# carousel.net
KiCad netlist of a schematic drawn in EAGLE
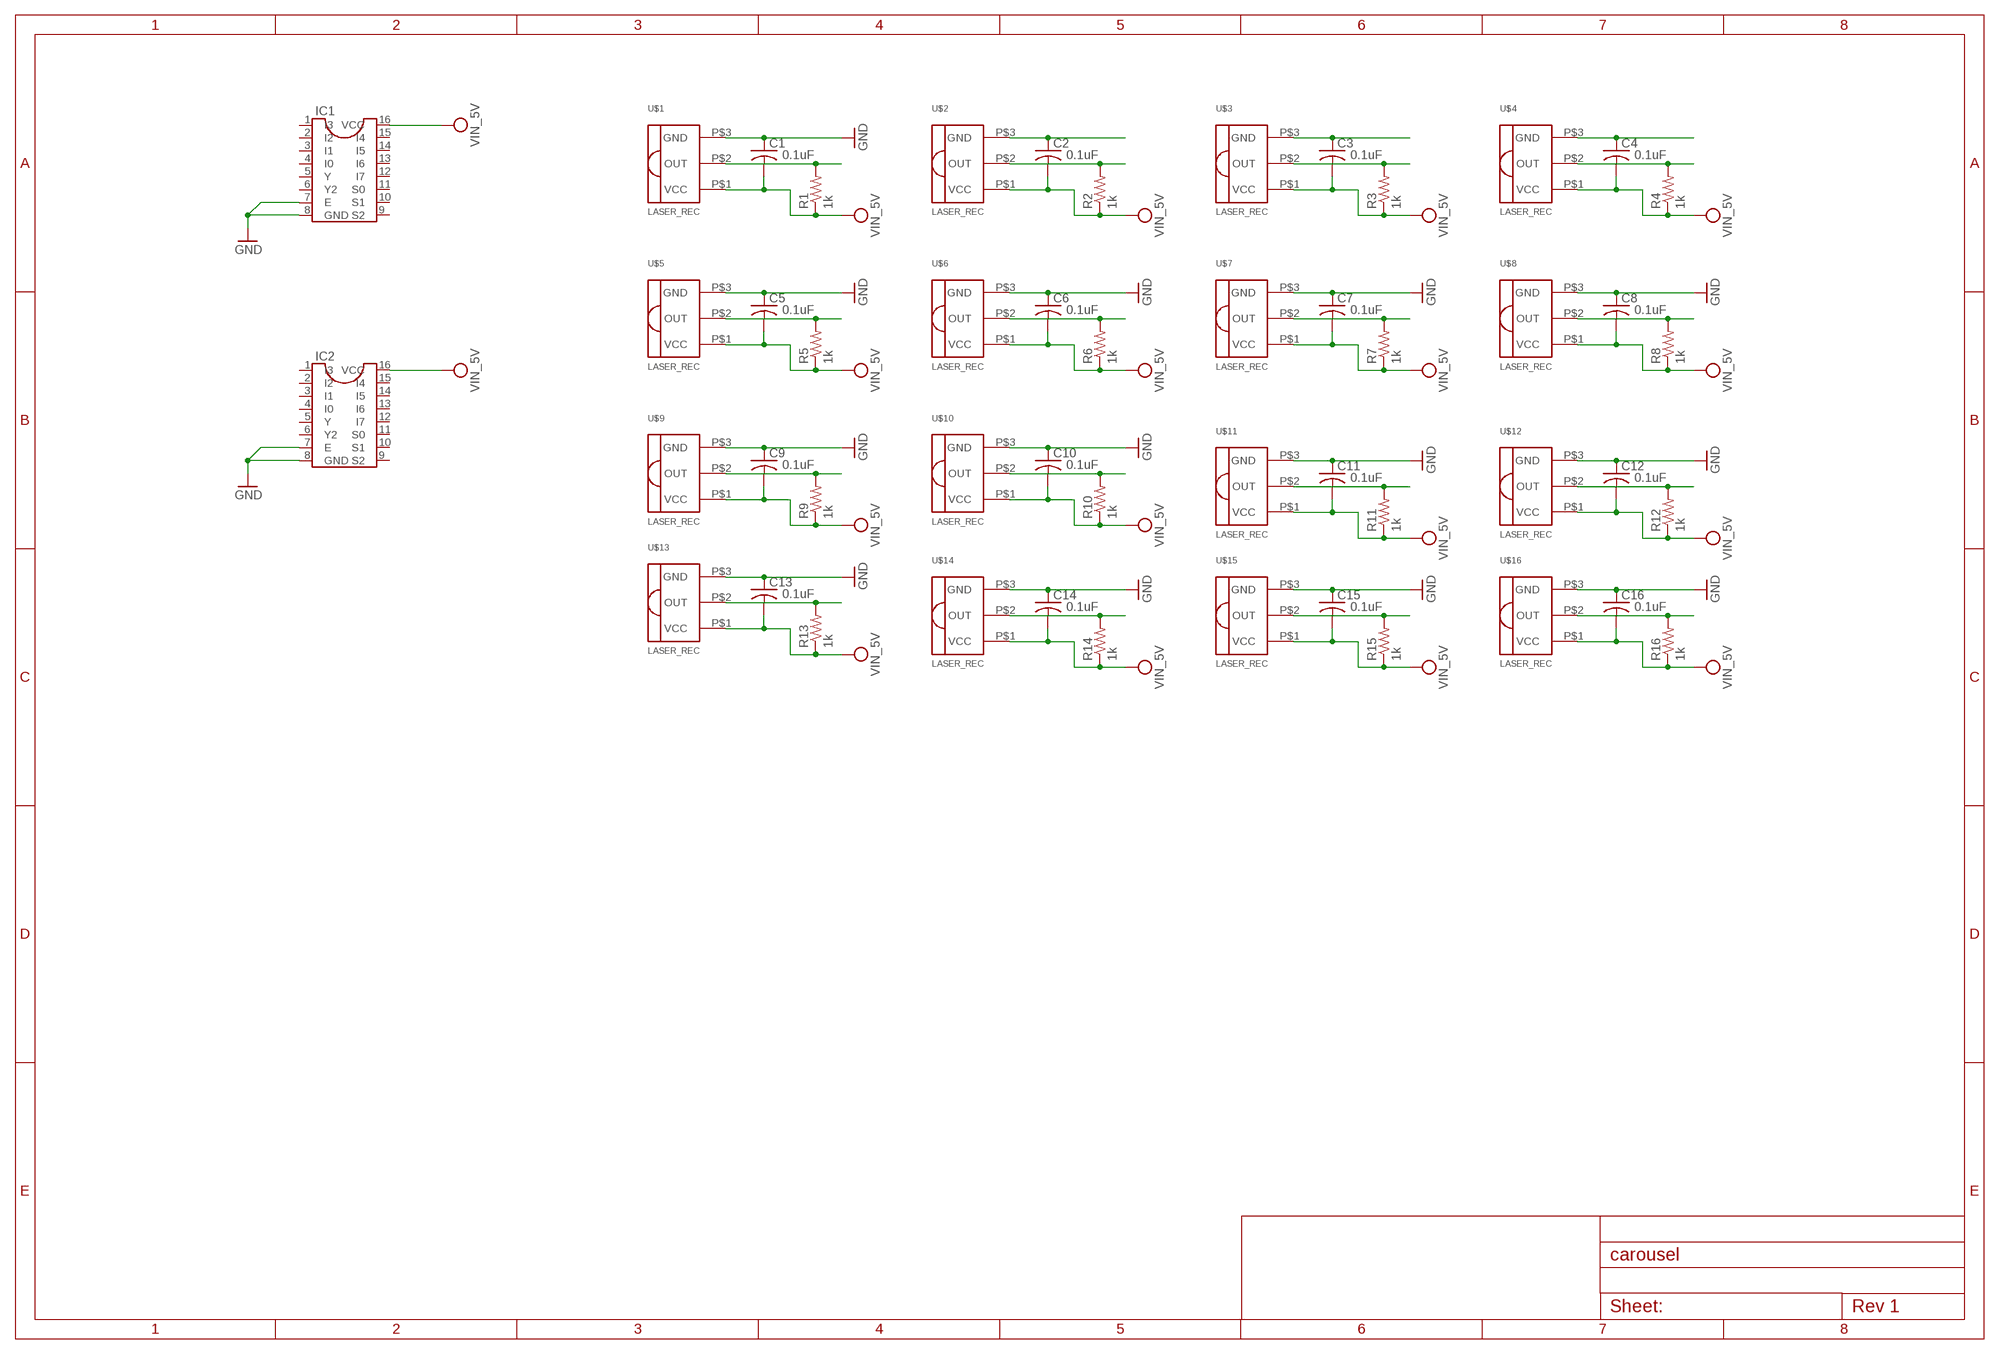
[diagram p0: schematic, sheet 1]

(export (version "E")
  (design (tool "Eeschema 10.0.6"))
  (components
    (comp (ref "C1")
      (value "0.1uF")
      (footprint "eagle-import:C025-024X044")
      (libsource (lib "eagle-import") (part "C-US025-024X044"))
    )
    (comp (ref "C2")
      (value "0.1uF")
      (footprint "eagle-import:C025-024X044")
      (libsource (lib "eagle-import") (part "C-US025-024X044"))
    )
    (comp (ref "C3")
      (value "0.1uF")
      (footprint "eagle-import:C025-024X044")
      (libsource (lib "eagle-import") (part "C-US025-024X044"))
    )
    (comp (ref "C4")
      (value "0.1uF")
      (footprint "eagle-import:C025-024X044")
      (libsource (lib "eagle-import") (part "C-US025-024X044"))
    )
    (comp (ref "C5")
      (value "0.1uF")
      (footprint "eagle-import:C025-024X044")
      (libsource (lib "eagle-import") (part "C-US025-024X044"))
    )
    (comp (ref "C6")
      (value "0.1uF")
      (footprint "eagle-import:C025-024X044")
      (libsource (lib "eagle-import") (part "C-US025-024X044"))
    )
    (comp (ref "C7")
      (value "0.1uF")
      (footprint "eagle-import:C025-024X044")
      (libsource (lib "eagle-import") (part "C-US025-024X044"))
    )
    (comp (ref "C8")
      (value "0.1uF")
      (footprint "eagle-import:C025-024X044")
      (libsource (lib "eagle-import") (part "C-US025-024X044"))
    )
    (comp (ref "C9")
      (value "0.1uF")
      (footprint "eagle-import:C025-024X044")
      (libsource (lib "eagle-import") (part "C-US025-024X044"))
    )
    (comp (ref "C10")
      (value "0.1uF")
      (footprint "eagle-import:C025-024X044")
      (libsource (lib "eagle-import") (part "C-US025-024X044"))
    )
    (comp (ref "C11")
      (value "0.1uF")
      (footprint "eagle-import:C025-024X044")
      (libsource (lib "eagle-import") (part "C-US025-024X044"))
    )
    (comp (ref "C12")
      (value "0.1uF")
      (footprint "eagle-import:C050-024X044")
      (libsource (lib "eagle-import") (part "C-US050-024X044"))
    )
    (comp (ref "C13")
      (value "0.1uF")
      (footprint "eagle-import:C025-024X044")
      (libsource (lib "eagle-import") (part "C-US025-024X044"))
    )
    (comp (ref "C14")
      (value "0.1uF")
      (footprint "eagle-import:C025-024X044")
      (libsource (lib "eagle-import") (part "C-US025-024X044"))
    )
    (comp (ref "C15")
      (value "0.1uF")
      (footprint "eagle-import:C025-024X044")
      (libsource (lib "eagle-import") (part "C-US025-024X044"))
    )
    (comp (ref "C16")
      (value "0.1uF")
      (footprint "eagle-import:C025-024X044")
      (libsource (lib "eagle-import") (part "C-US025-024X044"))
    )
    (comp (ref "IC1")
      (value "CD74HCT151S")
      (footprint "eagle-import:CD74HCT151")
      (libsource (lib "eagle-import") (part "CD74HCT151S"))
    )
    (comp (ref "IC2")
      (value "CD74HCT151S")
      (footprint "eagle-import:CD74HCT151")
      (libsource (lib "eagle-import") (part "CD74HCT151S"))
    )
    (comp (ref "R1")
      (value "1k")
      (footprint "eagle-import:0204V")
      (libsource (lib "eagle-import") (part "R-US_0204/2V"))
    )
    (comp (ref "R2")
      (value "1k")
      (footprint "eagle-import:0204V")
      (libsource (lib "eagle-import") (part "R-US_0204/2V"))
    )
    (comp (ref "R3")
      (value "1k")
      (footprint "eagle-import:0204V")
      (libsource (lib "eagle-import") (part "R-US_0204/2V"))
    )
    (comp (ref "R4")
      (value "1k")
      (footprint "eagle-import:0204V")
      (libsource (lib "eagle-import") (part "R-US_0204/2V"))
    )
    (comp (ref "R5")
      (value "1k")
      (footprint "eagle-import:0204V")
      (libsource (lib "eagle-import") (part "R-US_0204/2V"))
    )
    (comp (ref "R6")
      (value "1k")
      (footprint "eagle-import:0204V")
      (libsource (lib "eagle-import") (part "R-US_0204/2V"))
    )
    (comp (ref "R7")
      (value "1k")
      (footprint "eagle-import:0204V")
      (libsource (lib "eagle-import") (part "R-US_0204/2V"))
    )
    (comp (ref "R8")
      (value "1k")
      (footprint "eagle-import:0204V")
      (libsource (lib "eagle-import") (part "R-US_0204/2V"))
    )
    (comp (ref "R9")
      (value "1k")
      (footprint "eagle-import:0204V")
      (libsource (lib "eagle-import") (part "R-US_0204/2V"))
    )
    (comp (ref "R10")
      (value "1k")
      (footprint "eagle-import:0204V")
      (libsource (lib "eagle-import") (part "R-US_0204/2V"))
    )
    (comp (ref "R11")
      (value "1k")
      (footprint "eagle-import:0204V")
      (libsource (lib "eagle-import") (part "R-US_0204/2V"))
    )
    (comp (ref "R12")
      (value "1k")
      (footprint "eagle-import:0204V")
      (libsource (lib "eagle-import") (part "R-US_0204/2V"))
    )
    (comp (ref "R13")
      (value "1k")
      (footprint "eagle-import:0204V")
      (libsource (lib "eagle-import") (part "R-US_0204/2V"))
    )
    (comp (ref "R14")
      (value "1k")
      (footprint "eagle-import:0204V")
      (libsource (lib "eagle-import") (part "R-US_0204/2V"))
    )
    (comp (ref "R15")
      (value "1k")
      (footprint "eagle-import:0204V")
      (libsource (lib "eagle-import") (part "R-US_0204/2V"))
    )
    (comp (ref "R16")
      (value "1k")
      (footprint "eagle-import:0204V")
      (libsource (lib "eagle-import") (part "R-US_0204/2V"))
    )
    (comp (ref "U$1")
      (value "LASER_REC")
      (footprint "eagle-import:LSR_RC")
      (libsource (lib "eagle-import") (part "LASER_REC"))
    )
    (comp (ref "U$2")
      (value "LASER_REC")
      (footprint "eagle-import:LSR_RC")
      (libsource (lib "eagle-import") (part "LASER_REC"))
    )
    (comp (ref "U$3")
      (value "LASER_REC")
      (footprint "eagle-import:LSR_RC")
      (libsource (lib "eagle-import") (part "LASER_REC"))
    )
    (comp (ref "U$4")
      (value "LASER_REC")
      (footprint "eagle-import:LSR_RC")
      (libsource (lib "eagle-import") (part "LASER_REC"))
    )
    (comp (ref "U$5")
      (value "LASER_REC")
      (footprint "eagle-import:LSR_RC")
      (libsource (lib "eagle-import") (part "LASER_REC"))
    )
    (comp (ref "U$6")
      (value "LASER_REC")
      (footprint "eagle-import:LSR_RC")
      (libsource (lib "eagle-import") (part "LASER_REC"))
    )
    (comp (ref "U$7")
      (value "LASER_REC")
      (footprint "eagle-import:LSR_RC")
      (libsource (lib "eagle-import") (part "LASER_REC"))
    )
    (comp (ref "U$8")
      (value "LASER_REC")
      (footprint "eagle-import:LSR_RC")
      (libsource (lib "eagle-import") (part "LASER_REC"))
    )
    (comp (ref "U$9")
      (value "LASER_REC")
      (footprint "eagle-import:LSR_RC")
      (libsource (lib "eagle-import") (part "LASER_REC"))
    )
    (comp (ref "U$10")
      (value "LASER_REC")
      (footprint "eagle-import:LSR_RC")
      (libsource (lib "eagle-import") (part "LASER_REC"))
    )
    (comp (ref "U$11")
      (value "LASER_REC")
      (footprint "eagle-import:LSR_RC")
      (libsource (lib "eagle-import") (part "LASER_REC"))
    )
    (comp (ref "U$12")
      (value "LASER_REC")
      (footprint "eagle-import:LSR_RC")
      (libsource (lib "eagle-import") (part "LASER_REC"))
    )
    (comp (ref "U$13")
      (value "LASER_REC")
      (footprint "eagle-import:LSR_RC")
      (libsource (lib "eagle-import") (part "LASER_REC"))
    )
    (comp (ref "U$14")
      (value "LASER_REC")
      (footprint "eagle-import:LSR_RC")
      (libsource (lib "eagle-import") (part "LASER_REC"))
    )
    (comp (ref "U$15")
      (value "LASER_REC")
      (footprint "eagle-import:LSR_RC")
      (libsource (lib "eagle-import") (part "LASER_REC"))
    )
    (comp (ref "U$16")
      (value "LASER_REC")
      (footprint "eagle-import:LSR_RC")
      (libsource (lib "eagle-import") (part "LASER_REC"))
    )
  )
  (nets
    (net (code "1") (name "GND") (class "Default")
      (node (ref "C1") (pin "1") (pinfunction "1_1") (pintype "passive"))
      (node (ref "C10") (pin "1") (pinfunction "1_1") (pintype "passive"))
      (node (ref "C11") (pin "1") (pinfunction "1_1") (pintype "passive"))
      (node (ref "C12") (pin "1") (pinfunction "1_1") (pintype "passive"))
      (node (ref "C13") (pin "1") (pinfunction "1_1") (pintype "passive"))
      (node (ref "C14") (pin "1") (pinfunction "1_1") (pintype "passive"))
      (node (ref "C15") (pin "1") (pinfunction "1_1") (pintype "passive"))
      (node (ref "C16") (pin "1") (pinfunction "1_1") (pintype "passive"))
      (node (ref "C5") (pin "1") (pinfunction "1_1") (pintype "passive"))
      (node (ref "C6") (pin "1") (pinfunction "1_1") (pintype "passive"))
      (node (ref "C7") (pin "1") (pinfunction "1_1") (pintype "passive"))
      (node (ref "C8") (pin "1") (pinfunction "1_1") (pintype "passive"))
      (node (ref "C9") (pin "1") (pinfunction "1_1") (pintype "passive"))
      (node (ref "IC1") (pin "7") (pinfunction "E_7") (pintype "power_in"))
      (node (ref "IC1") (pin "8") (pinfunction "GND_8") (pintype "power_in"))
      (node (ref "IC2") (pin "7") (pinfunction "E_7") (pintype "power_in"))
      (node (ref "IC2") (pin "8") (pinfunction "GND_8") (pintype "power_in"))
      (node (ref "U$1") (pin "P$3") (pinfunction "GND_P$3") (pintype "power_in"))
      (node (ref "U$10") (pin "P$3") (pinfunction "GND_P$3") (pintype "power_in"))
      (node (ref "U$11") (pin "P$3") (pinfunction "GND_P$3") (pintype "power_in"))
      (node (ref "U$12") (pin "P$3") (pinfunction "GND_P$3") (pintype "power_in"))
      (node (ref "U$13") (pin "P$3") (pinfunction "GND_P$3") (pintype "power_in"))
      (node (ref "U$14") (pin "P$3") (pinfunction "GND_P$3") (pintype "power_in"))
      (node (ref "U$15") (pin "P$3") (pinfunction "GND_P$3") (pintype "power_in"))
      (node (ref "U$16") (pin "P$3") (pinfunction "GND_P$3") (pintype "power_in"))
      (node (ref "U$5") (pin "P$3") (pinfunction "GND_P$3") (pintype "power_in"))
      (node (ref "U$6") (pin "P$3") (pinfunction "GND_P$3") (pintype "power_in"))
      (node (ref "U$7") (pin "P$3") (pinfunction "GND_P$3") (pintype "power_in"))
      (node (ref "U$8") (pin "P$3") (pinfunction "GND_P$3") (pintype "power_in"))
      (node (ref "U$9") (pin "P$3") (pinfunction "GND_P$3") (pintype "power_in"))
    )
    (net (code "2") (name "Net-(U$1-OUT)") (class "Default")
      (node (ref "R1") (pin "2") (pinfunction "2_2") (pintype "passive"))
      (node (ref "U$1") (pin "P$2") (pinfunction "OUT_P$2") (pintype "output"))
    )
    (net (code "3") (name "Net-(U$2-GND)") (class "Default")
      (node (ref "C2") (pin "1") (pinfunction "1_1") (pintype "passive"))
      (node (ref "U$2") (pin "P$3") (pinfunction "GND_P$3") (pintype "power_in"))
    )
    (net (code "4") (name "Net-(U$2-OUT)") (class "Default")
      (node (ref "R2") (pin "2") (pinfunction "2_2") (pintype "passive"))
      (node (ref "U$2") (pin "P$2") (pinfunction "OUT_P$2") (pintype "output"))
    )
    (net (code "5") (name "Net-(U$3-GND)") (class "Default")
      (node (ref "C3") (pin "1") (pinfunction "1_1") (pintype "passive"))
      (node (ref "U$3") (pin "P$3") (pinfunction "GND_P$3") (pintype "power_in"))
    )
    (net (code "6") (name "Net-(U$3-OUT)") (class "Default")
      (node (ref "R3") (pin "2") (pinfunction "2_2") (pintype "passive"))
      (node (ref "U$3") (pin "P$2") (pinfunction "OUT_P$2") (pintype "output"))
    )
    (net (code "7") (name "Net-(U$4-GND)") (class "Default")
      (node (ref "C4") (pin "1") (pinfunction "1_1") (pintype "passive"))
      (node (ref "U$4") (pin "P$3") (pinfunction "GND_P$3") (pintype "power_in"))
    )
    (net (code "8") (name "Net-(U$4-OUT)") (class "Default")
      (node (ref "R4") (pin "2") (pinfunction "2_2") (pintype "passive"))
      (node (ref "U$4") (pin "P$2") (pinfunction "OUT_P$2") (pintype "output"))
    )
    (net (code "9") (name "Net-(U$5-OUT)") (class "Default")
      (node (ref "R5") (pin "2") (pinfunction "2_2") (pintype "passive"))
      (node (ref "U$5") (pin "P$2") (pinfunction "OUT_P$2") (pintype "output"))
    )
    (net (code "10") (name "Net-(U$6-OUT)") (class "Default")
      (node (ref "R6") (pin "2") (pinfunction "2_2") (pintype "passive"))
      (node (ref "U$6") (pin "P$2") (pinfunction "OUT_P$2") (pintype "output"))
    )
    (net (code "11") (name "Net-(U$7-OUT)") (class "Default")
      (node (ref "R7") (pin "2") (pinfunction "2_2") (pintype "passive"))
      (node (ref "U$7") (pin "P$2") (pinfunction "OUT_P$2") (pintype "output"))
    )
    (net (code "12") (name "Net-(U$8-OUT)") (class "Default")
      (node (ref "R8") (pin "2") (pinfunction "2_2") (pintype "passive"))
      (node (ref "U$8") (pin "P$2") (pinfunction "OUT_P$2") (pintype "output"))
    )
    (net (code "13") (name "Net-(U$9-OUT)") (class "Default")
      (node (ref "R9") (pin "2") (pinfunction "2_2") (pintype "passive"))
      (node (ref "U$9") (pin "P$2") (pinfunction "OUT_P$2") (pintype "output"))
    )
    (net (code "14") (name "Net-(U$10-OUT)") (class "Default")
      (node (ref "R10") (pin "2") (pinfunction "2_2") (pintype "passive"))
      (node (ref "U$10") (pin "P$2") (pinfunction "OUT_P$2") (pintype "output"))
    )
    (net (code "15") (name "Net-(U$11-OUT)") (class "Default")
      (node (ref "R11") (pin "2") (pinfunction "2_2") (pintype "passive"))
      (node (ref "U$11") (pin "P$2") (pinfunction "OUT_P$2") (pintype "output"))
    )
    (net (code "16") (name "Net-(U$12-OUT)") (class "Default")
      (node (ref "R12") (pin "2") (pinfunction "2_2") (pintype "passive"))
      (node (ref "U$12") (pin "P$2") (pinfunction "OUT_P$2") (pintype "output"))
    )
    (net (code "17") (name "Net-(U$13-OUT)") (class "Default")
      (node (ref "R13") (pin "2") (pinfunction "2_2") (pintype "passive"))
      (node (ref "U$13") (pin "P$2") (pinfunction "OUT_P$2") (pintype "output"))
    )
    (net (code "18") (name "Net-(U$14-OUT)") (class "Default")
      (node (ref "R14") (pin "2") (pinfunction "2_2") (pintype "passive"))
      (node (ref "U$14") (pin "P$2") (pinfunction "OUT_P$2") (pintype "output"))
    )
    (net (code "19") (name "Net-(U$15-OUT)") (class "Default")
      (node (ref "R15") (pin "2") (pinfunction "2_2") (pintype "passive"))
      (node (ref "U$15") (pin "P$2") (pinfunction "OUT_P$2") (pintype "output"))
    )
    (net (code "20") (name "Net-(U$16-OUT)") (class "Default")
      (node (ref "R16") (pin "2") (pinfunction "2_2") (pintype "passive"))
      (node (ref "U$16") (pin "P$2") (pinfunction "OUT_P$2") (pintype "output"))
    )
    (net (code "21") (name "VIN_5V") (class "Default")
      (node (ref "C1") (pin "2") (pinfunction "2_2") (pintype "passive"))
      (node (ref "C10") (pin "2") (pinfunction "2_2") (pintype "passive"))
      (node (ref "C11") (pin "2") (pinfunction "2_2") (pintype "passive"))
      (node (ref "C12") (pin "2") (pinfunction "2_2") (pintype "passive"))
      (node (ref "C13") (pin "2") (pinfunction "2_2") (pintype "passive"))
      (node (ref "C14") (pin "2") (pinfunction "2_2") (pintype "passive"))
      (node (ref "C15") (pin "2") (pinfunction "2_2") (pintype "passive"))
      (node (ref "C16") (pin "2") (pinfunction "2_2") (pintype "passive"))
      (node (ref "C2") (pin "2") (pinfunction "2_2") (pintype "passive"))
      (node (ref "C3") (pin "2") (pinfunction "2_2") (pintype "passive"))
      (node (ref "C4") (pin "2") (pinfunction "2_2") (pintype "passive"))
      (node (ref "C5") (pin "2") (pinfunction "2_2") (pintype "passive"))
      (node (ref "C6") (pin "2") (pinfunction "2_2") (pintype "passive"))
      (node (ref "C7") (pin "2") (pinfunction "2_2") (pintype "passive"))
      (node (ref "C8") (pin "2") (pinfunction "2_2") (pintype "passive"))
      (node (ref "C9") (pin "2") (pinfunction "2_2") (pintype "passive"))
      (node (ref "IC1") (pin "16") (pinfunction "VCC_16") (pintype "power_in"))
      (node (ref "IC2") (pin "16") (pinfunction "VCC_16") (pintype "power_in"))
      (node (ref "R1") (pin "1") (pinfunction "1_1") (pintype "passive"))
      (node (ref "R10") (pin "1") (pinfunction "1_1") (pintype "passive"))
      (node (ref "R11") (pin "1") (pinfunction "1_1") (pintype "passive"))
      (node (ref "R12") (pin "1") (pinfunction "1_1") (pintype "passive"))
      (node (ref "R13") (pin "1") (pinfunction "1_1") (pintype "passive"))
      (node (ref "R14") (pin "1") (pinfunction "1_1") (pintype "passive"))
      (node (ref "R15") (pin "1") (pinfunction "1_1") (pintype "passive"))
      (node (ref "R16") (pin "1") (pinfunction "1_1") (pintype "passive"))
      (node (ref "R2") (pin "1") (pinfunction "1_1") (pintype "passive"))
      (node (ref "R3") (pin "1") (pinfunction "1_1") (pintype "passive"))
      (node (ref "R4") (pin "1") (pinfunction "1_1") (pintype "passive"))
      (node (ref "R5") (pin "1") (pinfunction "1_1") (pintype "passive"))
      (node (ref "R6") (pin "1") (pinfunction "1_1") (pintype "passive"))
      (node (ref "R7") (pin "1") (pinfunction "1_1") (pintype "passive"))
      (node (ref "R8") (pin "1") (pinfunction "1_1") (pintype "passive"))
      (node (ref "R9") (pin "1") (pinfunction "1_1") (pintype "passive"))
      (node (ref "U$1") (pin "P$1") (pinfunction "VCC_P$1") (pintype "power_in"))
      (node (ref "U$10") (pin "P$1") (pinfunction "VCC_P$1") (pintype "power_in"))
      (node (ref "U$11") (pin "P$1") (pinfunction "VCC_P$1") (pintype "power_in"))
      (node (ref "U$12") (pin "P$1") (pinfunction "VCC_P$1") (pintype "power_in"))
      (node (ref "U$13") (pin "P$1") (pinfunction "VCC_P$1") (pintype "power_in"))
      (node (ref "U$14") (pin "P$1") (pinfunction "VCC_P$1") (pintype "power_in"))
      (node (ref "U$15") (pin "P$1") (pinfunction "VCC_P$1") (pintype "power_in"))
      (node (ref "U$16") (pin "P$1") (pinfunction "VCC_P$1") (pintype "power_in"))
      (node (ref "U$2") (pin "P$1") (pinfunction "VCC_P$1") (pintype "power_in"))
      (node (ref "U$3") (pin "P$1") (pinfunction "VCC_P$1") (pintype "power_in"))
      (node (ref "U$4") (pin "P$1") (pinfunction "VCC_P$1") (pintype "power_in"))
      (node (ref "U$5") (pin "P$1") (pinfunction "VCC_P$1") (pintype "power_in"))
      (node (ref "U$6") (pin "P$1") (pinfunction "VCC_P$1") (pintype "power_in"))
      (node (ref "U$7") (pin "P$1") (pinfunction "VCC_P$1") (pintype "power_in"))
      (node (ref "U$8") (pin "P$1") (pinfunction "VCC_P$1") (pintype "power_in"))
      (node (ref "U$9") (pin "P$1") (pinfunction "VCC_P$1") (pintype "power_in"))
    )
    (net (code "22") (name "unconnected-(IC1-I0-Pad4)") (class "Default")
      (node (ref "IC1") (pin "4") (pinfunction "I0_4") (pintype "input"))
    )
    (net (code "23") (name "unconnected-(IC1-I1-Pad3)") (class "Default")
      (node (ref "IC1") (pin "3") (pinfunction "I1_3") (pintype "input"))
    )
    (net (code "24") (name "unconnected-(IC1-I2-Pad2)") (class "Default")
      (node (ref "IC1") (pin "2") (pinfunction "I2_2") (pintype "input"))
    )
    (net (code "25") (name "unconnected-(IC1-I3-Pad1)") (class "Default")
      (node (ref "IC1") (pin "1") (pinfunction "I3_1") (pintype "input"))
    )
    (net (code "26") (name "unconnected-(IC1-I4-Pad15)") (class "Default")
      (node (ref "IC1") (pin "15") (pinfunction "I4_15") (pintype "input"))
    )
    (net (code "27") (name "unconnected-(IC1-I5-Pad14)") (class "Default")
      (node (ref "IC1") (pin "14") (pinfunction "I5_14") (pintype "input"))
    )
    (net (code "28") (name "unconnected-(IC1-I6-Pad13)") (class "Default")
      (node (ref "IC1") (pin "13") (pinfunction "I6_13") (pintype "input"))
    )
    (net (code "29") (name "unconnected-(IC1-I7-Pad12)") (class "Default")
      (node (ref "IC1") (pin "12") (pinfunction "I7_12") (pintype "input"))
    )
    (net (code "30") (name "unconnected-(IC1-S0-Pad11)") (class "Default")
      (node (ref "IC1") (pin "11") (pinfunction "S0_11") (pintype "input"))
    )
    (net (code "31") (name "unconnected-(IC1-S1-Pad10)") (class "Default")
      (node (ref "IC1") (pin "10") (pinfunction "S1_10") (pintype "input"))
    )
    (net (code "32") (name "unconnected-(IC1-S2-Pad9)") (class "Default")
      (node (ref "IC1") (pin "9") (pinfunction "S2_9") (pintype "input"))
    )
    (net (code "33") (name "unconnected-(IC1-Y-Pad5)") (class "Default")
      (node (ref "IC1") (pin "5") (pinfunction "Y_5") (pintype "output"))
    )
    (net (code "34") (name "unconnected-(IC1-Y2-Pad6)") (class "Default")
      (node (ref "IC1") (pin "6") (pinfunction "Y2_6") (pintype "output"))
    )
    (net (code "35") (name "unconnected-(IC2-I0-Pad4)") (class "Default")
      (node (ref "IC2") (pin "4") (pinfunction "I0_4") (pintype "input"))
    )
    (net (code "36") (name "unconnected-(IC2-I1-Pad3)") (class "Default")
      (node (ref "IC2") (pin "3") (pinfunction "I1_3") (pintype "input"))
    )
    (net (code "37") (name "unconnected-(IC2-I2-Pad2)") (class "Default")
      (node (ref "IC2") (pin "2") (pinfunction "I2_2") (pintype "input"))
    )
    (net (code "38") (name "unconnected-(IC2-I3-Pad1)") (class "Default")
      (node (ref "IC2") (pin "1") (pinfunction "I3_1") (pintype "input"))
    )
    (net (code "39") (name "unconnected-(IC2-I4-Pad15)") (class "Default")
      (node (ref "IC2") (pin "15") (pinfunction "I4_15") (pintype "input"))
    )
    (net (code "40") (name "unconnected-(IC2-I5-Pad14)") (class "Default")
      (node (ref "IC2") (pin "14") (pinfunction "I5_14") (pintype "input"))
    )
    (net (code "41") (name "unconnected-(IC2-I6-Pad13)") (class "Default")
      (node (ref "IC2") (pin "13") (pinfunction "I6_13") (pintype "input"))
    )
    (net (code "42") (name "unconnected-(IC2-I7-Pad12)") (class "Default")
      (node (ref "IC2") (pin "12") (pinfunction "I7_12") (pintype "input"))
    )
    (net (code "43") (name "unconnected-(IC2-S0-Pad11)") (class "Default")
      (node (ref "IC2") (pin "11") (pinfunction "S0_11") (pintype "input"))
    )
    (net (code "44") (name "unconnected-(IC2-S1-Pad10)") (class "Default")
      (node (ref "IC2") (pin "10") (pinfunction "S1_10") (pintype "input"))
    )
    (net (code "45") (name "unconnected-(IC2-S2-Pad9)") (class "Default")
      (node (ref "IC2") (pin "9") (pinfunction "S2_9") (pintype "input"))
    )
    (net (code "46") (name "unconnected-(IC2-Y-Pad5)") (class "Default")
      (node (ref "IC2") (pin "5") (pinfunction "Y_5") (pintype "output"))
    )
    (net (code "47") (name "unconnected-(IC2-Y2-Pad6)") (class "Default")
      (node (ref "IC2") (pin "6") (pinfunction "Y2_6") (pintype "output"))
    )
  )
)
